# Discharge_circuit.net
KiCad netlist of a schematic drawn in Altium Designer
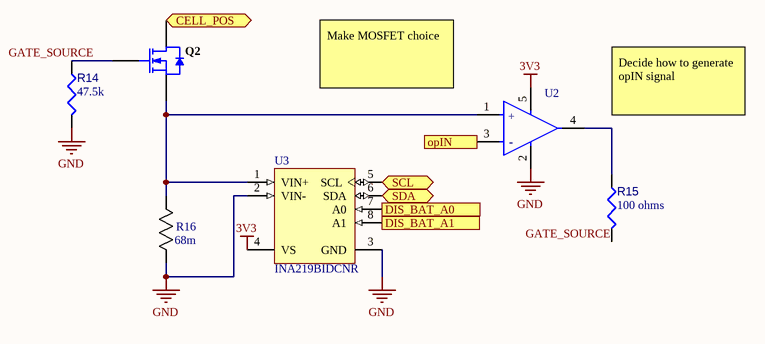
[diagram p0: Discharge_circuit.SchDoc]

(export (version "E")
  (design (tool "Eeschema 10.0.6"))
  (components
    (comp (ref "Q2")
      (value "FQD13N06LTM")
      (footprint "FAIR-TO-252-3_V")
      (fields (field (name "POWER") "2.5W") (field (name "MANUFACTURER") "Fairchild"))
      (libsource (lib "ZionTech") (part "NEMOS-GDS-3_A"))
    )
    (comp (ref "R14")
      (value "47.5k")
      (footprint "RESC0402(1005)_L")
      (description "Chip Resistor, 47,5 kOhms, +/-1 %, 63 mW, -55 to 155 degC, 0402")
      (fields (field (name "POWER") "63mW") (field (name "TOLERANCE") "1%"))
      (libsource (lib "ZionTech") (part "RES-2"))
    )
    (comp (ref "R15")
      (value "100 ohms")
      (footprint "RESC0402(1005)_L")
      (description "Chip Resistor, 100 Ohms, +/-1 %, 63 mW, -55 to 155 degC, 0402")
      (fields (field (name "POWER") "63mW") (field (name "TOLERANCE") "1%"))
      (libsource (lib "ZionTech") (part "RES-2"))
    )
    (comp (ref "R16")
      (value "68m")
      (footprint "YAG_R2512_YAG")
      (description "RL2512FK-070R068L")
      (fields (field (name "COPYRIGHT") "Copyright (C) 2026 Ultra Librarian. All rights reserved."))
      (libsource (lib "ZionTech") (part "RL2512FK-070R068L"))
    )
    (comp (ref "U2")
      (value "OPA391DCKT")
      (footprint "FP-DCK0005A-MFG")
      (description "IC OPAMP GP 1 CIRCUIT SC70-5")
      (libsource (lib "Altium Content Vault") (part "000f5c41575af8b8d083a31a5be8140"))
    )
    (comp (ref "U3")
      (value "INA219BIDCNR")
      (footprint "DCN0008A_M")
      (fields (field (name "MANUFACTURER") "Texas Instruments"))
      (libsource (lib "Altium Content Vault") (part "TI-INA219DCN8"))
    )
  )
  (nets
    (net (code "1") (name "/CELL_POS") (class "Default")
      (node (ref "Q2") (pin "4") (pinfunction "D_4") (pintype "passive"))
    )
    (net (code "2") (name "/DIS_BAT_A0") (class "Default")
      (node (ref "U3") (pin "7") (pinfunction "A0_7") (pintype "input"))
    )
    (net (code "3") (name "/DIS_BAT_A1") (class "Default")
      (node (ref "U3") (pin "8") (pinfunction "A1_8") (pintype "input"))
    )
    (net (code "4") (name "/GATE_SOURCE") (class "Default")
      (node (ref "Q2") (pin "1") (pinfunction "G_1") (pintype "passive"))
      (node (ref "R14") (pin "1") (pinfunction "1_1") (pintype "passive"))
      (node (ref "R15") (pin "2") (pinfunction "2_2") (pintype "passive"))
    )
    (net (code "5") (name "/SCL") (class "Default")
      (node (ref "U3") (pin "5") (pinfunction "SCL_5") (pintype "bidirectional"))
    )
    (net (code "6") (name "/SDA") (class "Default")
      (node (ref "U3") (pin "6") (pinfunction "SDA_6") (pintype "bidirectional"))
    )
    (net (code "7") (name "/opIN") (class "Default")
      (node (ref "U2") (pin "3") (pinfunction "-IN_3") (pintype "tri_state"))
    )
    (net (code "8") (name "3V3") (class "Default")
      (node (ref "U2") (pin "5") (pinfunction "V+_5") (pintype "power_in"))
      (node (ref "U3") (pin "4") (pinfunction "VS_4") (pintype "power_in"))
    )
    (net (code "9") (name "GND") (class "Default")
      (node (ref "R14") (pin "2") (pinfunction "2_2") (pintype "passive"))
      (node (ref "R16") (pin "2") (pinfunction "2_2") (pintype "passive"))
      (node (ref "U2") (pin "2") (pinfunction "V-_2") (pintype "power_in"))
      (node (ref "U3") (pin "2") (pinfunction "VIN-_2") (pintype "input"))
      (node (ref "U3") (pin "3") (pinfunction "GND_3") (pintype "power_in"))
    )
    (net (code "10") (name "Net-(Q2-S)") (class "Default")
      (node (ref "Q2") (pin "3") (pinfunction "S_3") (pintype "passive"))
      (node (ref "R16") (pin "1") (pinfunction "1_1") (pintype "passive"))
      (node (ref "U2") (pin "1") (pinfunction "+IN_1") (pintype "tri_state"))
      (node (ref "U3") (pin "1") (pinfunction "VIN+_1") (pintype "input"))
    )
    (net (code "11") (name "Net-(U2-OUT)") (class "Default")
      (node (ref "R15") (pin "1") (pinfunction "1_1") (pintype "passive"))
      (node (ref "U2") (pin "4") (pinfunction "OUT_4") (pintype "passive"))
    )
  )
)
